# YLXC.net
KiCad netlist of a schematic drawn in Altium Designer
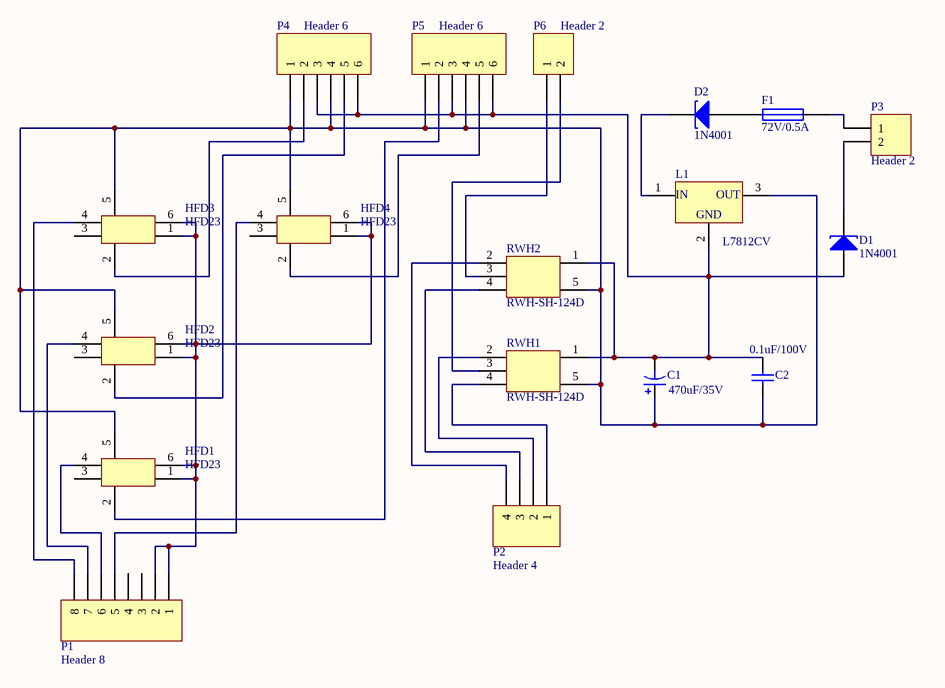
[diagram p0: YLXC.SchDoc]

(export (version "E")
  (design (tool "Eeschema 10.0.6"))
  (components
    (comp (ref "C1")
      (value "470uF/35V")
      (footprint "Cap Pol2")
      (description "Polarized Capacitor (Axial)")
      (fields (field (name "Comment") "Cap Pol2") (field (name "PUBLISHER") "Altium Limited"))
      (libsource (lib "YLXC") (part "Cap Pol2"))
    )
    (comp (ref "C2")
      (value "0.1uF/100V")
      (footprint "Cap")
      (description "Capacitor")
      (fields (field (name "Comment") "Cap") (field (name "PUBLISHER") "Altium Limited"))
      (libsource (lib "YLXC") (part "Cap"))
    )
    (comp (ref "D1")
      (value "1N4001")
      (footprint "DIODE-0.4")
      (description "Tunnel Diode - Dependent Source Model")
      (fields (field (name "PUBLISHER") "Altium Limited"))
      (libsource (lib "Miscellaneous Devices") (part "D Tunnel2"))
    )
    (comp (ref "D2")
      (value "1N4001")
      (footprint "DIODE-0.4")
      (description "Tunnel Diode - Dependent Source Model")
      (fields (field (name "PUBLISHER") "Altium Limited"))
      (libsource (lib "Miscellaneous Devices") (part "D Tunnel2"))
    )
    (comp (ref "F1")
      (value "72V/0.5A")
      (footprint "Fuse 1")
      (description "Fuse")
      (fields (field (name "PUBLISHER") "Altium Limited"))
      (libsource (lib "YLXC") (part "Fuse 1"))
    )
    (comp (ref "HFD1") (value "HFD23") (footprint "HFD23 012-12S") (libsource (lib "YLXC") (part "HFD23")))
    (comp (ref "HFD2") (value "HFD23") (footprint "HFD23 012-12S") (libsource (lib "YLXC") (part "HFD23")))
    (comp (ref "HFD3") (value "HFD23") (footprint "HFD23 012-12S") (libsource (lib "YLXC") (part "HFD23")))
    (comp (ref "HFD4") (value "HFD23") (footprint "HFD23 012-12S") (libsource (lib "YLXC") (part "HFD23")))
    (comp (ref "L1") (value "L7812CV") (footprint "LM7812") (libsource (lib "YLXC") (part "LM7812")))
    (comp (ref "P1")
      (value "Header 8")
      (footprint "HDR1X8")
      (description "Header, 8-Pin")
      (fields (field (name "PUBLISHER") "Altium Limited"))
      (libsource (lib "Miscellaneous Connectors") (part "Header 8"))
    )
    (comp (ref "P2")
      (value "Header 4")
      (footprint "HDR1X4")
      (description "Header, 4-Pin")
      (fields (field (name "PUBLISHER") "Altium Limited"))
      (libsource (lib "Miscellaneous Connectors") (part "Header 4"))
    )
    (comp (ref "P3")
      (value "Header 2")
      (footprint "HDR1X2")
      (description "Header, 2-Pin")
      (fields (field (name "PUBLISHER") "Altium Limited"))
      (libsource (lib "") (part "Header 2_1"))
    )
    (comp (ref "P4")
      (value "Header 6")
      (footprint "HDR1X6")
      (description "Header, 6-Pin")
      (fields (field (name "PUBLISHER") "Altium Limited"))
      (libsource (lib "Miscellaneous Connectors") (part "Header 6"))
    )
    (comp (ref "P5")
      (value "Header 6")
      (footprint "HDR1X6")
      (description "Header, 6-Pin")
      (fields (field (name "PUBLISHER") "Altium Limited"))
      (libsource (lib "Miscellaneous Connectors") (part "Header 6"))
    )
    (comp (ref "P6")
      (value "Header 2")
      (footprint "HDR1X2")
      (description "Header, 2-Pin")
      (fields (field (name "PUBLISHER") "Altium Limited"))
      (libsource (lib "Miscellaneous Connectors") (part "Header 2"))
    )
    (comp (ref "RWH1")
      (value "RWH-SH-124D")
      (footprint "RWH-SH-124D")
      (libsource (lib "YLXC") (part "RWH-SH-124D"))
    )
    (comp (ref "RWH2")
      (value "RWH-SH-124D")
      (footprint "RWH-SH-124D")
      (libsource (lib "YLXC") (part "RWH-SH-124D"))
    )
  )
  (nets
    (net (code "1") (name "Net-(C1-Pad1)") (class "Default")
      (node (ref "C1") (pin "1") (pinfunction "1_1") (pintype "passive"))
      (node (ref "C2") (pin "1") (pinfunction "1_1") (pintype "passive"))
      (node (ref "HFD1") (pin "5") (pinfunction "5_5") (pintype "passive"))
      (node (ref "HFD2") (pin "5") (pinfunction "5_5") (pintype "passive"))
      (node (ref "HFD3") (pin "5") (pinfunction "5_5") (pintype "passive"))
      (node (ref "HFD4") (pin "5") (pinfunction "5_5") (pintype "passive"))
      (node (ref "L1") (pin "3") (pinfunction "3_3") (pintype "passive"))
      (node (ref "P4") (pin "1") (pinfunction "1_1") (pintype "passive"))
      (node (ref "P4") (pin "4") (pinfunction "4_4") (pintype "passive"))
      (node (ref "P5") (pin "1") (pinfunction "1_1") (pintype "passive"))
      (node (ref "P5") (pin "4") (pinfunction "4_4") (pintype "passive"))
      (node (ref "RWH1") (pin "5") (pinfunction "5_5") (pintype "passive"))
      (node (ref "RWH2") (pin "5") (pinfunction "5_5") (pintype "passive"))
    )
    (net (code "2") (name "Net-(D1-A)") (class "Default")
      (node (ref "C1") (pin "2") (pinfunction "2_2") (pintype "passive"))
      (node (ref "C2") (pin "2") (pinfunction "2_2") (pintype "passive"))
      (node (ref "D1") (pin "1") (pinfunction "A_1") (pintype "passive"))
      (node (ref "L1") (pin "2") (pinfunction "2_2") (pintype "passive"))
      (node (ref "P4") (pin "3") (pinfunction "3_3") (pintype "passive"))
      (node (ref "P4") (pin "6") (pinfunction "6_6") (pintype "passive"))
      (node (ref "P5") (pin "3") (pinfunction "3_3") (pintype "passive"))
      (node (ref "P5") (pin "6") (pinfunction "6_6") (pintype "passive"))
      (node (ref "RWH1") (pin "1") (pinfunction "6_1") (pintype "passive"))
      (node (ref "RWH2") (pin "1") (pinfunction "6_1") (pintype "passive"))
    )
    (net (code "3") (name "Net-(D1-K)") (class "Default")
      (node (ref "D1") (pin "2") (pinfunction "K_2") (pintype "passive"))
      (node (ref "P3") (pin "2") (pinfunction "2_2") (pintype "passive"))
    )
    (net (code "4") (name "Net-(D2-A)") (class "Default")
      (node (ref "D2") (pin "1") (pinfunction "A_1") (pintype "passive"))
      (node (ref "F1") (pin "1") (pinfunction "1_1") (pintype "passive"))
    )
    (net (code "5") (name "Net-(D2-K)") (class "Default")
      (node (ref "D2") (pin "2") (pinfunction "K_2") (pintype "passive"))
      (node (ref "L1") (pin "1") (pintype "passive"))
    )
    (net (code "6") (name "Net-(F1-Pad2)") (class "Default")
      (node (ref "F1") (pin "2") (pinfunction "2_2") (pintype "passive"))
      (node (ref "P3") (pin "1") (pinfunction "1_1") (pintype "passive"))
    )
    (net (code "7") (name "Net-(HFD1-Pad1)") (class "Default")
      (node (ref "HFD1") (pin "1") (pinfunction "1_1") (pintype "passive"))
      (node (ref "HFD1") (pin "6") (pinfunction "6_6") (pintype "passive"))
      (node (ref "HFD2") (pin "1") (pinfunction "1_1") (pintype "passive"))
      (node (ref "HFD2") (pin "6") (pinfunction "6_6") (pintype "passive"))
      (node (ref "HFD3") (pin "1") (pinfunction "1_1") (pintype "passive"))
      (node (ref "HFD3") (pin "6") (pinfunction "6_6") (pintype "passive"))
      (node (ref "HFD4") (pin "1") (pinfunction "1_1") (pintype "passive"))
      (node (ref "HFD4") (pin "6") (pinfunction "6_6") (pintype "passive"))
      (node (ref "P1") (pin "1") (pinfunction "1_1") (pintype "passive"))
      (node (ref "P1") (pin "2") (pinfunction "2_2") (pintype "passive"))
    )
    (net (code "8") (name "Net-(HFD1-Pad2)") (class "Default")
      (node (ref "HFD1") (pin "2") (pinfunction "2_2") (pintype "passive"))
      (node (ref "P5") (pin "2") (pinfunction "2_2") (pintype "passive"))
    )
    (net (code "9") (name "Net-(HFD1-Pad4)") (class "Default")
      (node (ref "HFD1") (pin "4") (pinfunction "4_4") (pintype "passive"))
      (node (ref "P1") (pin "6") (pinfunction "6_6") (pintype "passive"))
    )
    (net (code "10") (name "Net-(HFD2-Pad2)") (class "Default")
      (node (ref "HFD2") (pin "2") (pinfunction "2_2") (pintype "passive"))
      (node (ref "P4") (pin "5") (pinfunction "5_5") (pintype "passive"))
    )
    (net (code "11") (name "Net-(HFD2-Pad4)") (class "Default")
      (node (ref "HFD2") (pin "4") (pinfunction "4_4") (pintype "passive"))
      (node (ref "P1") (pin "7") (pinfunction "7_7") (pintype "passive"))
    )
    (net (code "12") (name "Net-(HFD3-Pad2)") (class "Default")
      (node (ref "HFD3") (pin "2") (pinfunction "2_2") (pintype "passive"))
      (node (ref "P4") (pin "2") (pinfunction "2_2") (pintype "passive"))
    )
    (net (code "13") (name "Net-(HFD3-Pad4)") (class "Default")
      (node (ref "HFD3") (pin "4") (pinfunction "4_4") (pintype "passive"))
      (node (ref "P1") (pin "8") (pinfunction "8_8") (pintype "passive"))
    )
    (net (code "14") (name "Net-(HFD4-Pad2)") (class "Default")
      (node (ref "HFD4") (pin "2") (pinfunction "2_2") (pintype "passive"))
      (node (ref "P5") (pin "5") (pinfunction "5_5") (pintype "passive"))
    )
    (net (code "15") (name "Net-(HFD4-Pad4)") (class "Default")
      (node (ref "HFD4") (pin "4") (pinfunction "4_4") (pintype "passive"))
      (node (ref "P1") (pin "5") (pinfunction "5_5") (pintype "passive"))
    )
    (net (code "16") (name "Net-(P2-Pad1)") (class "Default")
      (node (ref "P2") (pin "1") (pinfunction "1_1") (pintype "passive"))
      (node (ref "RWH1") (pin "4") (pinfunction "4_4") (pintype "passive"))
    )
    (net (code "17") (name "Net-(P2-Pad2)") (class "Default")
      (node (ref "P2") (pin "2") (pinfunction "2_2") (pintype "passive"))
      (node (ref "RWH1") (pin "2") (pinfunction "1_2") (pintype "passive"))
    )
    (net (code "18") (name "Net-(P2-Pad3)") (class "Default")
      (node (ref "P2") (pin "3") (pinfunction "3_3") (pintype "passive"))
      (node (ref "RWH2") (pin "4") (pinfunction "4_4") (pintype "passive"))
    )
    (net (code "19") (name "Net-(P2-Pad4)") (class "Default")
      (node (ref "P2") (pin "4") (pinfunction "4_4") (pintype "passive"))
      (node (ref "RWH2") (pin "2") (pinfunction "1_2") (pintype "passive"))
    )
    (net (code "20") (name "Net-(P6-Pad1)") (class "Default")
      (node (ref "P6") (pin "1") (pinfunction "1_1") (pintype "passive"))
      (node (ref "RWH2") (pin "3") (pinfunction "1_3") (pintype "passive"))
    )
    (net (code "21") (name "Net-(P6-Pad2)") (class "Default")
      (node (ref "P6") (pin "2") (pinfunction "2_2") (pintype "passive"))
      (node (ref "RWH1") (pin "3") (pinfunction "1_3") (pintype "passive"))
    )
    (net (code "22") (name "unconnected-(HFD1-Pad3)") (class "Default")
      (node (ref "HFD1") (pin "3") (pinfunction "3_3") (pintype "passive"))
    )
    (net (code "23") (name "unconnected-(HFD2-Pad3)") (class "Default")
      (node (ref "HFD2") (pin "3") (pinfunction "3_3") (pintype "passive"))
    )
    (net (code "24") (name "unconnected-(HFD3-Pad3)") (class "Default")
      (node (ref "HFD3") (pin "3") (pinfunction "3_3") (pintype "passive"))
    )
    (net (code "25") (name "unconnected-(HFD4-Pad3)") (class "Default")
      (node (ref "HFD4") (pin "3") (pinfunction "3_3") (pintype "passive"))
    )
    (net (code "26") (name "unconnected-(P1-Pad3)") (class "Default")
      (node (ref "P1") (pin "3") (pinfunction "3_3") (pintype "passive"))
    )
    (net (code "27") (name "unconnected-(P1-Pad4)") (class "Default")
      (node (ref "P1") (pin "4") (pinfunction "4_4") (pintype "passive"))
    )
  )
)
